# Conncetors.net
KiCad netlist of a schematic drawn in Altium Designer
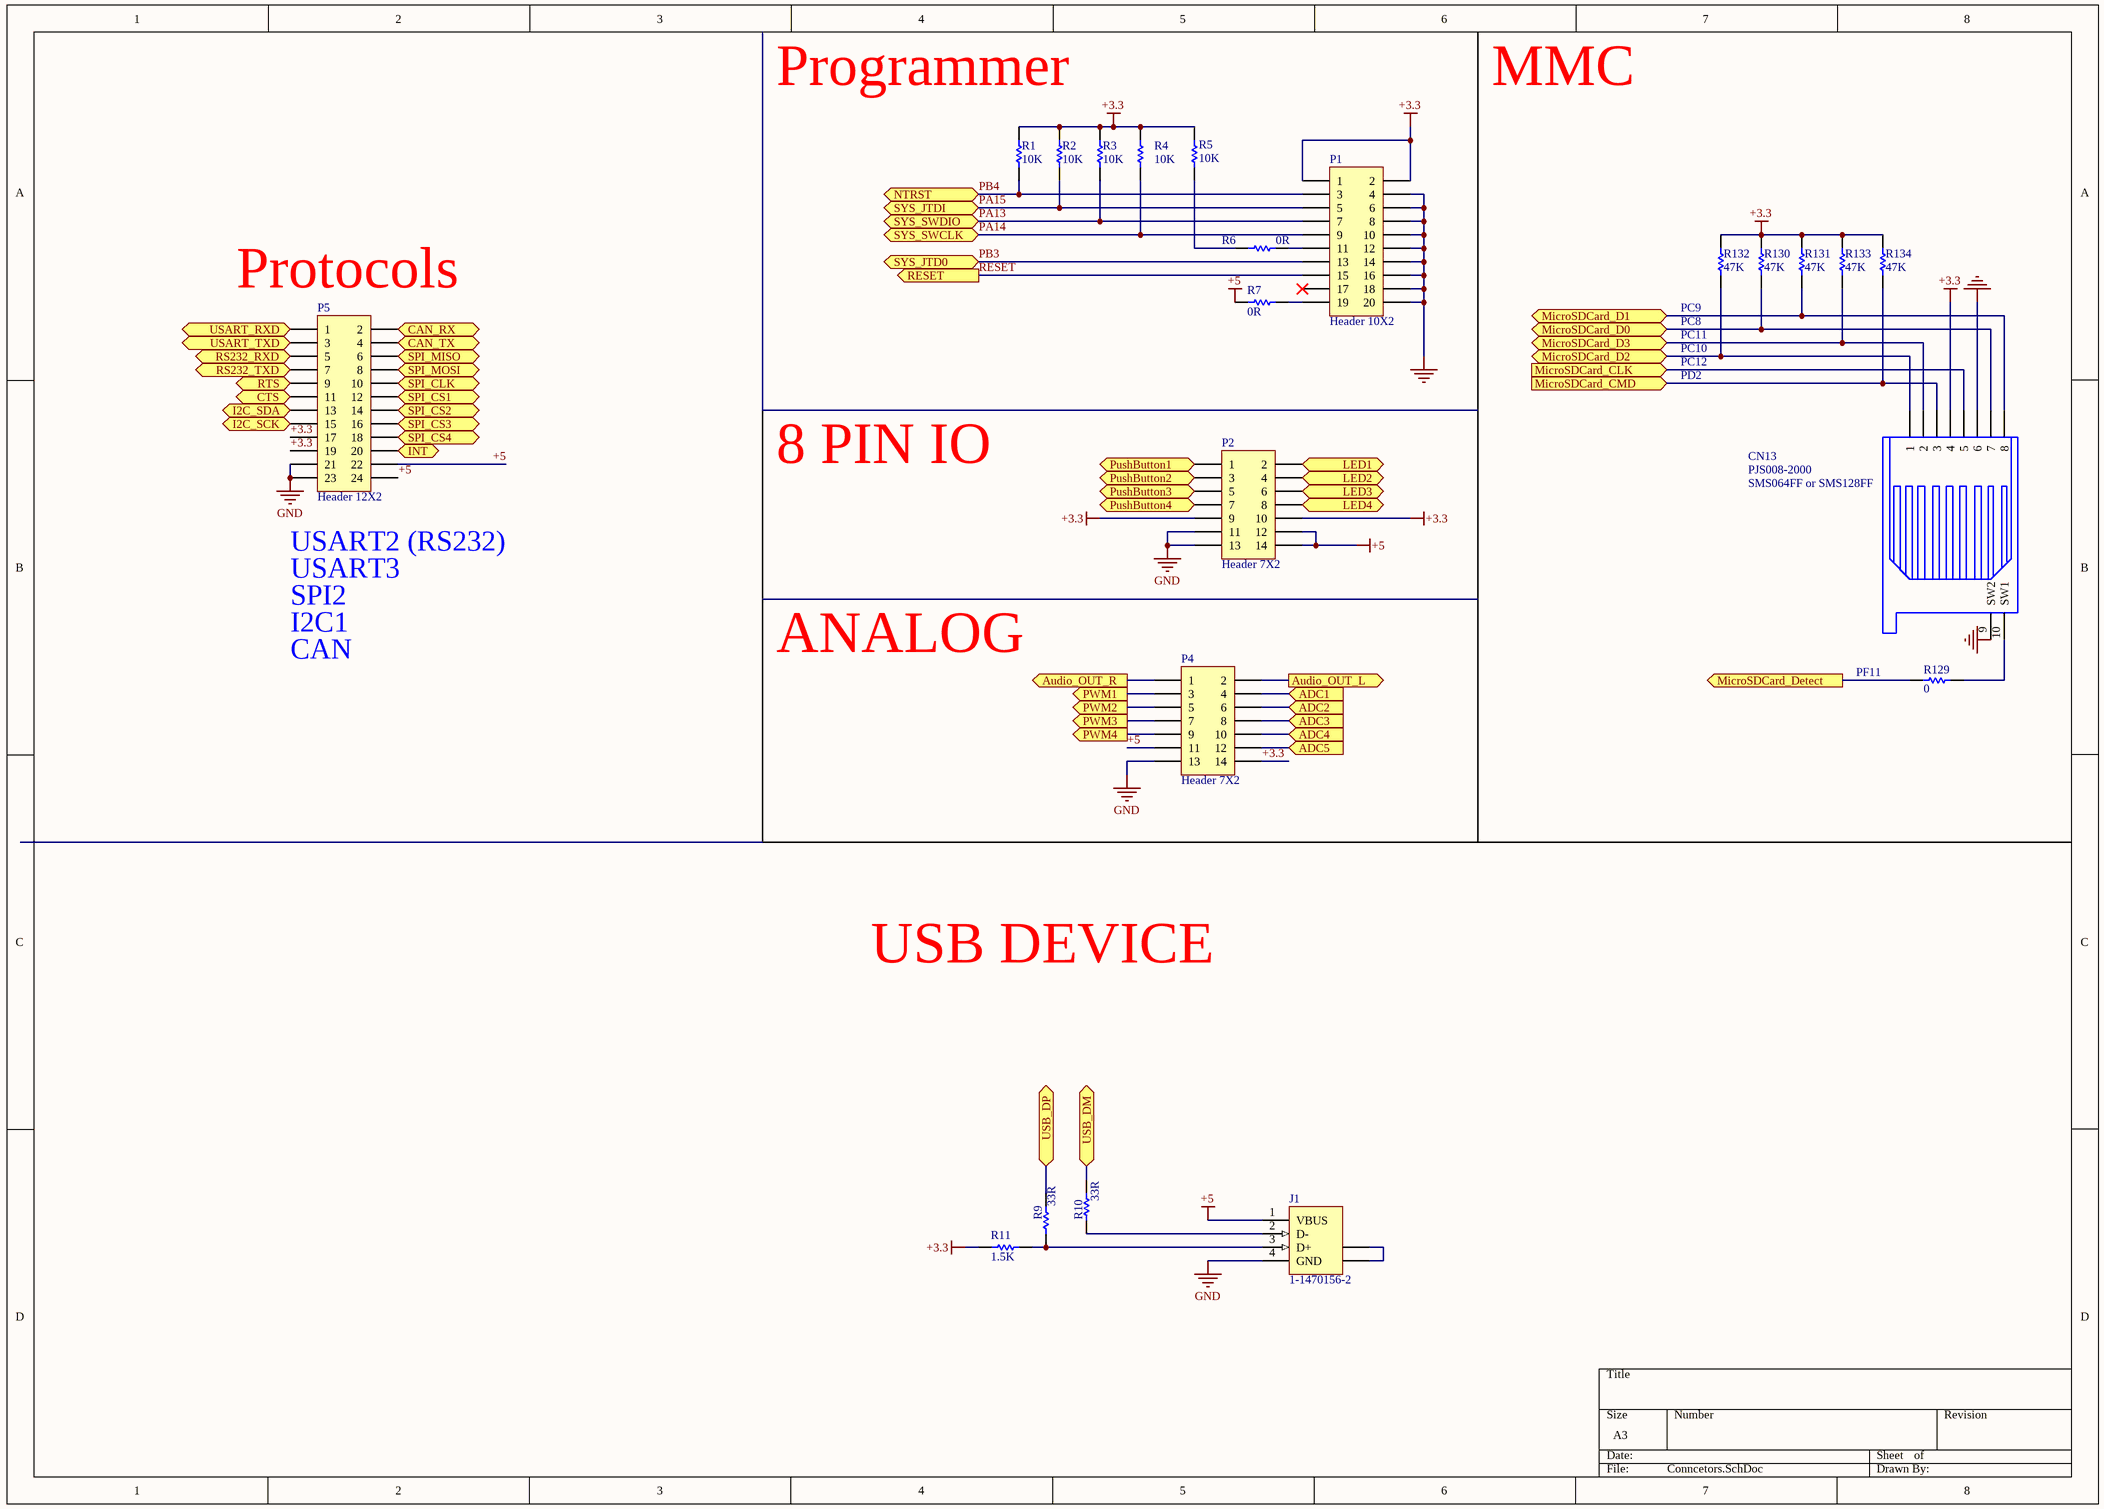
[diagram p0: Conncetors.SchDoc]

(export (version "E")
  (design (tool "Eeschema 10.0.6"))
  (components
    (comp (ref "CN13")
      (value "PJS008-2000")
      (footprint "MicroSD_1")
      (libsource (lib "MB525") (part "SMS016AFA5E"))
    )
    (comp (ref "J1")
      (value "1-1470156-2")
      (footprint "440247")
      (description "USB 1.1, Right Angle, Thru-Hole, B Type, Receptacle, 4 Position, Black")
      (fields (field (name "PUBLISHER") "Altium Limited"))
      (libsource (lib "AMP Serial Bus USB") (part "1-1470156-2"))
    )
    (comp (ref "P1")
      (value "Header 10X2")
      (footprint "IDC20S")
      (description "Header, 10-Pin, Dual row")
      (fields (field (name "PUBLISHER") "Altium Limited"))
      (libsource (lib "Miscellaneous Connectors") (part "Header 10X2"))
    )
    (comp (ref "P2")
      (value "Header 7X2")
      (footprint "IDC14S")
      (description "Header, 7-Pin, Dual row")
      (fields (field (name "PUBLISHER") "Altium Limited"))
      (libsource (lib "Miscellaneous Connectors") (part "Header 7X2"))
    )
    (comp (ref "P4")
      (value "Header 7X2")
      (footprint "IDC14S")
      (description "Header, 7-Pin, Dual row")
      (fields (field (name "PUBLISHER") "Altium Limited"))
      (libsource (lib "Miscellaneous Connectors") (part "Header 7X2"))
    )
    (comp (ref "P5")
      (value "Header 12X2")
      (footprint "IDC24S")
      (description "Header, 12-Pin, Dual row")
      (fields (field (name "PUBLISHER") "Altium Limited"))
      (libsource (lib "Miscellaneous Connectors") (part "Header 12X2"))
    )
    (comp (ref "R1")
      (value "10K")
      (footprint "1206")
      (description "Resistor")
      (fields (field (name "PUBLISHER") "Altium Limited"))
      (libsource (lib "Miscellaneous Devices") (part "Res1"))
    )
    (comp (ref "R2")
      (value "10K")
      (footprint "1206")
      (description "Resistor")
      (fields (field (name "PUBLISHER") "Altium Limited"))
      (libsource (lib "Miscellaneous Devices") (part "Res1"))
    )
    (comp (ref "R3")
      (value "10K")
      (footprint "1206")
      (description "Resistor")
      (fields (field (name "PUBLISHER") "Altium Limited"))
      (libsource (lib "Miscellaneous Devices") (part "Res1"))
    )
    (comp (ref "R4")
      (value "10K")
      (footprint "1206")
      (description "Resistor")
      (fields (field (name "PUBLISHER") "Altium Limited"))
      (libsource (lib "Miscellaneous Devices") (part "Res1"))
    )
    (comp (ref "R5")
      (value "10K")
      (footprint "1206")
      (description "Resistor")
      (fields (field (name "PUBLISHER") "Altium Limited"))
      (libsource (lib "Miscellaneous Devices") (part "Res1"))
    )
    (comp (ref "R6")
      (value "0R")
      (footprint "1206")
      (description "Resistor")
      (fields (field (name "PUBLISHER") "Altium Limited"))
      (libsource (lib "Miscellaneous Devices") (part "Res1"))
    )
    (comp (ref "R7")
      (value "0R")
      (footprint "1206")
      (description "Resistor")
      (fields (field (name "PUBLISHER") "Altium Limited"))
      (libsource (lib "Miscellaneous Devices") (part "Res1"))
    )
    (comp (ref "R9")
      (value "33R")
      (footprint "1206")
      (description "Resistor")
      (fields (field (name "PUBLISHER") "Altium Limited"))
      (libsource (lib "") (part "Res1_1"))
    )
    (comp (ref "R10")
      (value "33R")
      (footprint "1206")
      (description "Resistor")
      (fields (field (name "PUBLISHER") "Altium Limited"))
      (libsource (lib "") (part "Res1_1"))
    )
    (comp (ref "R11")
      (value "1.5K")
      (footprint "1206")
      (description "Resistor")
      (fields (field (name "PUBLISHER") "Altium Limited"))
      (libsource (lib "") (part "Res1_1"))
    )
    (comp (ref "R129")
      (value "0")
      (description "Resistor")
      (fields (field (name "PUBLISHER") "Altium Limited"))
      (libsource (lib "Miscellaneous Devices") (part "Res1"))
    )
    (comp (ref "R130")
      (value "47K")
      (description "Resistor")
      (fields (field (name "PUBLISHER") "Altium Limited"))
      (libsource (lib "Miscellaneous Devices") (part "Res1"))
    )
    (comp (ref "R131")
      (value "47K")
      (description "Resistor")
      (fields (field (name "PUBLISHER") "Altium Limited"))
      (libsource (lib "Miscellaneous Devices") (part "Res1"))
    )
    (comp (ref "R132")
      (value "47K")
      (description "Resistor")
      (fields (field (name "PUBLISHER") "Altium Limited"))
      (libsource (lib "Miscellaneous Devices") (part "Res1"))
    )
    (comp (ref "R133")
      (value "47K")
      (description "Resistor")
      (fields (field (name "PUBLISHER") "Altium Limited"))
      (libsource (lib "Miscellaneous Devices") (part "Res1"))
    )
    (comp (ref "R134")
      (value "47K")
      (description "Resistor")
      (fields (field (name "PUBLISHER") "Altium Limited"))
      (libsource (lib "Miscellaneous Devices") (part "Res1"))
    )
  )
  (nets
    (net (code "1") (name "+3.3") (class "Default")
      (node (ref "CN13") (pin "4") (pinfunction "4_4") (pintype "passive"))
      (node (ref "P1") (pin "1") (pinfunction "1_1") (pintype "passive"))
      (node (ref "P1") (pin "2") (pinfunction "2_2") (pintype "passive"))
      (node (ref "P2") (pin "10") (pinfunction "10_10") (pintype "passive"))
      (node (ref "P2") (pin "9") (pinfunction "9_9") (pintype "passive"))
      (node (ref "P4") (pin "14") (pinfunction "14_14") (pintype "passive"))
      (node (ref "P5") (pin "17") (pinfunction "17_17") (pintype "passive"))
      (node (ref "P5") (pin "19") (pinfunction "19_19") (pintype "passive"))
      (node (ref "R1") (pin "2") (pinfunction "2_2") (pintype "passive"))
      (node (ref "R11") (pin "1") (pinfunction "1_1") (pintype "passive"))
      (node (ref "R130") (pin "1") (pinfunction "1_1") (pintype "passive"))
      (node (ref "R131") (pin "1") (pinfunction "1_1") (pintype "passive"))
      (node (ref "R132") (pin "1") (pinfunction "1_1") (pintype "passive"))
      (node (ref "R133") (pin "1") (pinfunction "1_1") (pintype "passive"))
      (node (ref "R134") (pin "1") (pinfunction "1_1") (pintype "passive"))
      (node (ref "R2") (pin "2") (pinfunction "2_2") (pintype "passive"))
      (node (ref "R3") (pin "2") (pinfunction "2_2") (pintype "passive"))
      (node (ref "R4") (pin "2") (pinfunction "2_2") (pintype "passive"))
      (node (ref "R5") (pin "2") (pinfunction "2_2") (pintype "passive"))
    )
    (net (code "2") (name "+5") (class "Default")
      (node (ref "J1") (pin "1") (pinfunction "VBUS_1") (pintype "power_in"))
      (node (ref "P2") (pin "12") (pinfunction "12_12") (pintype "passive"))
      (node (ref "P2") (pin "14") (pinfunction "14_14") (pintype "passive"))
      (node (ref "P4") (pin "11") (pinfunction "11_11") (pintype "passive"))
      (node (ref "P5") (pin "22") (pinfunction "22_22") (pintype "passive"))
      (node (ref "P5") (pin "24") (pinfunction "24_24") (pintype "passive"))
      (node (ref "R7") (pin "2") (pinfunction "2_2") (pintype "passive"))
    )
    (net (code "3") (name "/ADC1") (class "Default")
      (node (ref "P4") (pin "4") (pinfunction "4_4") (pintype "passive"))
    )
    (net (code "4") (name "/ADC2") (class "Default")
      (node (ref "P4") (pin "6") (pinfunction "6_6") (pintype "passive"))
    )
    (net (code "5") (name "/ADC3") (class "Default")
      (node (ref "P4") (pin "8") (pinfunction "8_8") (pintype "passive"))
    )
    (net (code "6") (name "/ADC4") (class "Default")
      (node (ref "P4") (pin "10") (pinfunction "10_10") (pintype "passive"))
    )
    (net (code "7") (name "/ADC5") (class "Default")
      (node (ref "P4") (pin "12") (pinfunction "12_12") (pintype "passive"))
    )
    (net (code "8") (name "/Audio_OUT_L") (class "Default")
      (node (ref "P4") (pin "2") (pinfunction "2_2") (pintype "passive"))
    )
    (net (code "9") (name "/Audio_OUT_R") (class "Default")
      (node (ref "P4") (pin "1") (pinfunction "1_1") (pintype "passive"))
    )
    (net (code "10") (name "/CAN_RX") (class "Default")
      (node (ref "P5") (pin "2") (pinfunction "2_2") (pintype "passive"))
    )
    (net (code "11") (name "/CAN_TX") (class "Default")
      (node (ref "P5") (pin "4") (pinfunction "4_4") (pintype "passive"))
    )
    (net (code "12") (name "/CTS") (class "Default")
      (node (ref "P5") (pin "11") (pinfunction "11_11") (pintype "passive"))
    )
    (net (code "13") (name "/I2C_SCK") (class "Default")
      (node (ref "P5") (pin "15") (pinfunction "15_15") (pintype "passive"))
    )
    (net (code "14") (name "/I2C_SDA") (class "Default")
      (node (ref "P5") (pin "13") (pinfunction "13_13") (pintype "passive"))
    )
    (net (code "15") (name "/INT") (class "Default")
      (node (ref "P5") (pin "20") (pinfunction "20_20") (pintype "passive"))
    )
    (net (code "16") (name "/LED1") (class "Default")
      (node (ref "P2") (pin "2") (pinfunction "2_2") (pintype "passive"))
    )
    (net (code "17") (name "/LED2") (class "Default")
      (node (ref "P2") (pin "4") (pinfunction "4_4") (pintype "passive"))
    )
    (net (code "18") (name "/LED3") (class "Default")
      (node (ref "P2") (pin "6") (pinfunction "6_6") (pintype "passive"))
    )
    (net (code "19") (name "/LED4") (class "Default")
      (node (ref "P2") (pin "8") (pinfunction "8_8") (pintype "passive"))
    )
    (net (code "20") (name "/MicroSDCard_CLK") (class "Default")
      (node (ref "CN13") (pin "5") (pinfunction "5_5") (pintype "passive"))
    )
    (net (code "21") (name "/MicroSDCard_CMD") (class "Default")
      (node (ref "CN13") (pin "3") (pinfunction "3_3") (pintype "passive"))
      (node (ref "R134") (pin "2") (pinfunction "2_2") (pintype "passive"))
    )
    (net (code "22") (name "/MicroSDCard_D0") (class "Default")
      (node (ref "CN13") (pin "7") (pinfunction "7_7") (pintype "passive"))
      (node (ref "R130") (pin "2") (pinfunction "2_2") (pintype "passive"))
    )
    (net (code "23") (name "/MicroSDCard_D1") (class "Default")
      (node (ref "CN13") (pin "8") (pinfunction "8_8") (pintype "passive"))
      (node (ref "R131") (pin "2") (pinfunction "2_2") (pintype "passive"))
    )
    (net (code "24") (name "/MicroSDCard_D2") (class "Default")
      (node (ref "CN13") (pin "1") (pinfunction "1_1") (pintype "passive"))
      (node (ref "R132") (pin "2") (pinfunction "2_2") (pintype "passive"))
    )
    (net (code "25") (name "/MicroSDCard_D3") (class "Default")
      (node (ref "CN13") (pin "2") (pinfunction "2_2") (pintype "passive"))
      (node (ref "R133") (pin "2") (pinfunction "2_2") (pintype "passive"))
    )
    (net (code "26") (name "/MicroSDCard_Detect") (class "Default")
      (node (ref "R129") (pin "1") (pinfunction "1_1") (pintype "passive"))
    )
    (net (code "27") (name "/PA13") (class "Default")
      (node (ref "P1") (pin "7") (pinfunction "7_7") (pintype "passive"))
      (node (ref "R3") (pin "1") (pinfunction "1_1") (pintype "passive"))
    )
    (net (code "28") (name "/PA14") (class "Default")
      (node (ref "P1") (pin "9") (pinfunction "9_9") (pintype "passive"))
      (node (ref "R4") (pin "1") (pinfunction "1_1") (pintype "passive"))
    )
    (net (code "29") (name "/PA15") (class "Default")
      (node (ref "P1") (pin "5") (pinfunction "5_5") (pintype "passive"))
      (node (ref "R2") (pin "1") (pinfunction "1_1") (pintype "passive"))
    )
    (net (code "30") (name "/PB3") (class "Default")
      (node (ref "P1") (pin "13") (pinfunction "13_13") (pintype "passive"))
    )
    (net (code "31") (name "/PB4") (class "Default")
      (node (ref "P1") (pin "3") (pinfunction "3_3") (pintype "passive"))
      (node (ref "R1") (pin "1") (pinfunction "1_1") (pintype "passive"))
    )
    (net (code "32") (name "/PWM1") (class "Default")
      (node (ref "P4") (pin "3") (pinfunction "3_3") (pintype "passive"))
    )
    (net (code "33") (name "/PWM2") (class "Default")
      (node (ref "P4") (pin "5") (pinfunction "5_5") (pintype "passive"))
    )
    (net (code "34") (name "/PWM3") (class "Default")
      (node (ref "P4") (pin "7") (pinfunction "7_7") (pintype "passive"))
    )
    (net (code "35") (name "/PWM4") (class "Default")
      (node (ref "P4") (pin "9") (pinfunction "9_9") (pintype "passive"))
    )
    (net (code "36") (name "/PushButton1") (class "Default")
      (node (ref "P2") (pin "1") (pinfunction "1_1") (pintype "passive"))
    )
    (net (code "37") (name "/PushButton2") (class "Default")
      (node (ref "P2") (pin "3") (pinfunction "3_3") (pintype "passive"))
    )
    (net (code "38") (name "/PushButton3") (class "Default")
      (node (ref "P2") (pin "5") (pinfunction "5_5") (pintype "passive"))
    )
    (net (code "39") (name "/PushButton4") (class "Default")
      (node (ref "P2") (pin "7") (pinfunction "7_7") (pintype "passive"))
    )
    (net (code "40") (name "/RESET") (class "Default")
      (node (ref "P1") (pin "15") (pinfunction "15_15") (pintype "passive"))
    )
    (net (code "41") (name "/RS232_RXD") (class "Default")
      (node (ref "P5") (pin "5") (pinfunction "5_5") (pintype "passive"))
    )
    (net (code "42") (name "/RS232_TXD") (class "Default")
      (node (ref "P5") (pin "7") (pinfunction "7_7") (pintype "passive"))
    )
    (net (code "43") (name "/RTS") (class "Default")
      (node (ref "P5") (pin "9") (pinfunction "9_9") (pintype "passive"))
    )
    (net (code "44") (name "/SPI_CLK") (class "Default")
      (node (ref "P5") (pin "10") (pinfunction "10_10") (pintype "passive"))
    )
    (net (code "45") (name "/SPI_CS1") (class "Default")
      (node (ref "P5") (pin "12") (pinfunction "12_12") (pintype "passive"))
    )
    (net (code "46") (name "/SPI_CS2") (class "Default")
      (node (ref "P5") (pin "14") (pinfunction "14_14") (pintype "passive"))
    )
    (net (code "47") (name "/SPI_CS3") (class "Default")
      (node (ref "P5") (pin "16") (pinfunction "16_16") (pintype "passive"))
    )
    (net (code "48") (name "/SPI_CS4") (class "Default")
      (node (ref "P5") (pin "18") (pinfunction "18_18") (pintype "passive"))
    )
    (net (code "49") (name "/SPI_MISO") (class "Default")
      (node (ref "P5") (pin "6") (pinfunction "6_6") (pintype "passive"))
    )
    (net (code "50") (name "/SPI_MOSI") (class "Default")
      (node (ref "P5") (pin "8") (pinfunction "8_8") (pintype "passive"))
    )
    (net (code "51") (name "/USART_RXD") (class "Default")
      (node (ref "P5") (pin "1") (pinfunction "1_1") (pintype "passive"))
    )
    (net (code "52") (name "/USART_TXD") (class "Default")
      (node (ref "P5") (pin "3") (pinfunction "3_3") (pintype "passive"))
    )
    (net (code "53") (name "/USB_DM") (class "Default")
      (node (ref "R10") (pin "1") (pinfunction "1_1") (pintype "passive"))
    )
    (net (code "54") (name "/USB_DP") (class "Default")
      (node (ref "R9") (pin "1") (pinfunction "1_1") (pintype "passive"))
    )
    (net (code "55") (name "GND") (class "Default")
      (node (ref "CN13") (pin "6") (pinfunction "6_6") (pintype "passive"))
      (node (ref "CN13") (pin "9") (pinfunction "SW2_9") (pintype "passive"))
      (node (ref "J1") (pin "4") (pinfunction "GND_4") (pintype "power_in"))
      (node (ref "P1") (pin "10") (pinfunction "10_10") (pintype "passive"))
      (node (ref "P1") (pin "12") (pinfunction "12_12") (pintype "passive"))
      (node (ref "P1") (pin "14") (pinfunction "14_14") (pintype "passive"))
      (node (ref "P1") (pin "16") (pinfunction "16_16") (pintype "passive"))
      (node (ref "P1") (pin "18") (pinfunction "18_18") (pintype "passive"))
      (node (ref "P1") (pin "20") (pinfunction "20_20") (pintype "passive"))
      (node (ref "P1") (pin "4") (pinfunction "4_4") (pintype "passive"))
      (node (ref "P1") (pin "6") (pinfunction "6_6") (pintype "passive"))
      (node (ref "P1") (pin "8") (pinfunction "8_8") (pintype "passive"))
      (node (ref "P2") (pin "11") (pinfunction "11_11") (pintype "passive"))
      (node (ref "P2") (pin "13") (pinfunction "13_13") (pintype "passive"))
      (node (ref "P4") (pin "13") (pinfunction "13_13") (pintype "passive"))
      (node (ref "P5") (pin "21") (pinfunction "21_21") (pintype "passive"))
      (node (ref "P5") (pin "23") (pinfunction "23_23") (pintype "passive"))
    )
    (net (code "56") (name "Net-(CN13-SW1)") (class "Default")
      (node (ref "CN13") (pin "10") (pinfunction "SW1_10") (pintype "passive"))
      (node (ref "R129") (pin "2") (pinfunction "2_2") (pintype "passive"))
    )
    (net (code "57") (name "Net-(J1-D+)") (class "Default")
      (node (ref "J1") (pin "3") (pinfunction "D+_3") (pintype "input"))
      (node (ref "R11") (pin "2") (pinfunction "2_2") (pintype "passive"))
      (node (ref "R9") (pin "2") (pinfunction "2_2") (pintype "passive"))
    )
    (net (code "58") (name "Net-(J1-D-)") (class "Default")
      (node (ref "J1") (pin "2") (pinfunction "D-_2") (pintype "input"))
      (node (ref "R10") (pin "2") (pinfunction "2_2") (pintype "passive"))
    )
    (net (code "59") (name "Net-(J1-SHLD-Pad5)") (class "Default")
      (node (ref "J1") (pin "5") (pinfunction "SHLD_5") (pintype "passive"))
      (node (ref "J1") (pin "6") (pinfunction "SHLD_6") (pintype "passive"))
    )
    (net (code "60") (name "Net-(P1-Pad11)") (class "Default")
      (node (ref "P1") (pin "11") (pinfunction "11_11") (pintype "passive"))
      (node (ref "R6") (pin "1") (pinfunction "1_1") (pintype "passive"))
    )
    (net (code "61") (name "Net-(P1-Pad19)") (class "Default")
      (node (ref "P1") (pin "19") (pinfunction "19_19") (pintype "passive"))
      (node (ref "R7") (pin "1") (pinfunction "1_1") (pintype "passive"))
    )
    (net (code "62") (name "Net-(R5-Pad1)") (class "Default")
      (node (ref "R5") (pin "1") (pinfunction "1_1") (pintype "passive"))
      (node (ref "R6") (pin "2") (pinfunction "2_2") (pintype "passive"))
    )
    (net (code "63") (name "unconnected-(P1-Pad17)") (class "Default")
      (node (ref "P1") (pin "17") (pinfunction "17_17") (pintype "passive+no_connect"))
    )
  )
)
